# ThermocoupleAmplifiersAD8497.net
KiCad netlist of a schematic drawn in Altium Designer
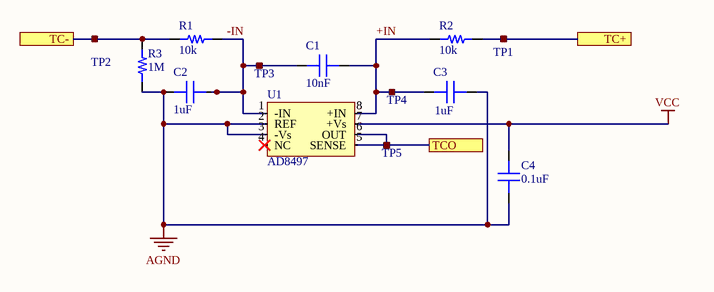
[diagram p0: ThermocoupleAmplifiersAD8497.SchDoc]

(export (version "E")
  (design (tool "Eeschema 10.0.6"))
  (components
    (comp (ref "C1")
      (value "capacitor")
      (footprint "0603")
      (description "Generic 0603 capacitor")
      (fields (field (name "CAPACITANCE") "10nF") (field (name "VOLTAGE") "50"))
      (libsource (lib "altlib") (part "capacitor"))
    )
    (comp (ref "C2")
      (value "capacitor")
      (footprint "0603")
      (description "Generic 0603 capacitor")
      (fields (field (name "CAPACITANCE") "1uF") (field (name "VOLTAGE") "50"))
      (libsource (lib "altlib") (part "capacitor"))
    )
    (comp (ref "C3")
      (value "capacitor")
      (footprint "0603")
      (description "Generic 0603 capacitor")
      (fields (field (name "CAPACITANCE") "1uF") (field (name "VOLTAGE") "50"))
      (libsource (lib "altlib") (part "capacitor"))
    )
    (comp (ref "C4")
      (value "capacitor")
      (footprint "0603")
      (description "Generic 0603 capacitor")
      (fields (field (name "CAPACITANCE") "0.1uF") (field (name "VOLTAGE") "50"))
      (libsource (lib "altlib") (part "capacitor"))
    )
    (comp (ref "R1")
      (value "10k")
      (footprint "RES 0603/1608")
      (fields (field (name "RESISTANCE") "10k"))
      (libsource (lib "altlib") (part "Resistor"))
    )
    (comp (ref "R2")
      (value "10k")
      (footprint "RES 0603/1608")
      (fields (field (name "RESISTANCE") "10k"))
      (libsource (lib "altlib") (part "Resistor"))
    )
    (comp (ref "R3")
      (value "1M")
      (footprint "RES 0603/1608")
      (fields (field (name "RESISTANCE") "1M"))
      (libsource (lib "altlib") (part "Resistor"))
    )
    (comp (ref "TP1") (value "RCU-0C") (footprint "RCU-0C") (libsource (lib "altlib") (part "RCU-0C")))
    (comp (ref "TP2") (value "RCU-0C") (footprint "RCU-0C") (libsource (lib "altlib") (part "RCU-0C")))
    (comp (ref "TP3") (value "RCU-0C") (footprint "RCU-0C") (libsource (lib "altlib") (part "RCU-0C")))
    (comp (ref "TP4") (value "RCU-0C") (footprint "RCU-0C") (libsource (lib "altlib") (part "RCU-0C")))
    (comp (ref "TP5") (value "RCU-0C") (footprint "RCU-0C") (libsource (lib "altlib") (part "RCU-0C")))
    (comp (ref "U1")
      (value "AD8497")
      (footprint "MSOP-8")
      (fields (field (name "VOLTAGE") "15"))
      (libsource (lib "altlib") (part "AD8494"))
    )
  )
  (nets
    (net (code "1") (name "/+IN") (class "Default")
      (node (ref "C1") (pin "2") (pinfunction "2_2") (pintype "passive"))
      (node (ref "C3") (pin "1") (pinfunction "1_1") (pintype "passive"))
      (node (ref "R2") (pin "1") (pinfunction "1_1") (pintype "passive"))
      (node (ref "TP4") (pin "1") (pintype "passive"))
      (node (ref "U1") (pin "8") (pinfunction "+IN_8") (pintype "input"))
    )
    (net (code "2") (name "/-IN") (class "Default")
      (node (ref "C1") (pin "1") (pinfunction "1_1") (pintype "passive"))
      (node (ref "C2") (pin "2") (pinfunction "2_2") (pintype "passive"))
      (node (ref "R1") (pin "2") (pinfunction "2_2") (pintype "passive"))
      (node (ref "TP3") (pin "1") (pintype "passive"))
      (node (ref "U1") (pin "1") (pinfunction "-IN_1") (pintype "input"))
    )
    (net (code "3") (name "/TC+") (class "Default")
      (node (ref "R2") (pin "2") (pinfunction "2_2") (pintype "passive"))
      (node (ref "TP1") (pin "1") (pintype "passive"))
    )
    (net (code "4") (name "/TC-") (class "Default")
      (node (ref "R1") (pin "1") (pinfunction "1_1") (pintype "passive"))
      (node (ref "R3") (pin "2") (pinfunction "2_2") (pintype "passive"))
      (node (ref "TP2") (pin "1") (pintype "passive"))
    )
    (net (code "5") (name "/TCO") (class "Default")
      (node (ref "TP5") (pin "1") (pintype "passive"))
      (node (ref "U1") (pin "5") (pinfunction "SENSE_5") (pintype "input"))
      (node (ref "U1") (pin "6") (pinfunction "OUT_6") (pintype "output"))
    )
    (net (code "6") (name "AGND") (class "Default")
      (node (ref "C2") (pin "1") (pinfunction "1_1") (pintype "passive"))
      (node (ref "C3") (pin "2") (pinfunction "2_2") (pintype "passive"))
      (node (ref "C4") (pin "1") (pinfunction "1_1") (pintype "passive"))
      (node (ref "R3") (pin "1") (pinfunction "1_1") (pintype "passive"))
      (node (ref "U1") (pin "2") (pinfunction "REF_2") (pintype "input"))
      (node (ref "U1") (pin "3") (pinfunction "-Vs_3") (pintype "power_in"))
    )
    (net (code "7") (name "VCC") (class "Default")
      (node (ref "C4") (pin "2") (pinfunction "2_2") (pintype "passive"))
      (node (ref "U1") (pin "7") (pinfunction "+Vs_7") (pintype "power_in"))
    )
    (net (code "8") (name "unconnected-(U1-NC-Pad4)") (class "Default")
      (node (ref "U1") (pin "4") (pinfunction "NC_4") (pintype "passive+no_connect"))
    )
  )
)
